# untitled.net
KiCad netlist of a schematic drawn in EAGLE
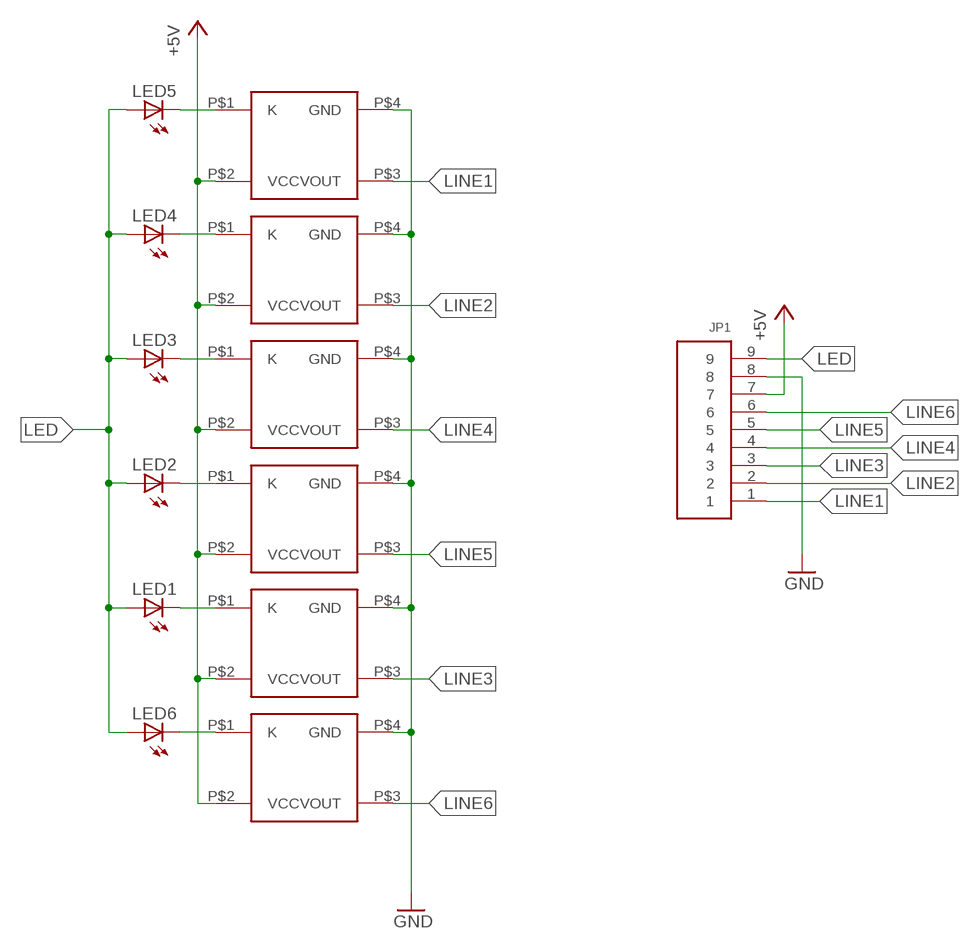
[diagram p0: schematic, sheet 1]

(export (version "E")
  (design (tool "Eeschema 10.0.6"))
  (components
    (comp (ref "JP1")
      (value "9PIN")
      (footprint "eagle-import:B9B-PH-K-S")
      (libsource (lib "eagle-import") (part "9PIN"))
    )
    (comp (ref "LED1")
      (value "LED5MM")
      (footprint "eagle-import:LED5MM")
      (libsource (lib "eagle-import") (part "LED5MM"))
    )
    (comp (ref "LED2")
      (value "LED5MM")
      (footprint "eagle-import:LED5MM")
      (libsource (lib "eagle-import") (part "LED5MM"))
    )
    (comp (ref "LED3")
      (value "LED5MM")
      (footprint "eagle-import:LED5MM")
      (libsource (lib "eagle-import") (part "LED5MM"))
    )
    (comp (ref "LED4")
      (value "LED5MM")
      (footprint "eagle-import:LED5MM")
      (libsource (lib "eagle-import") (part "LED5MM"))
    )
    (comp (ref "LED5")
      (value "LED5MM")
      (footprint "eagle-import:LED5MM")
      (libsource (lib "eagle-import") (part "LED5MM"))
    )
    (comp (ref "LED6")
      (value "LED5MM")
      (footprint "eagle-import:LED5MM")
      (libsource (lib "eagle-import") (part "LED5MM"))
    )
    (comp (ref "U$1")
      (value "S4282-51")
      (footprint "eagle-import:S4282-51")
      (libsource (lib "eagle-import") (part "S4282-51"))
    )
    (comp (ref "U$2")
      (value "S4282-51")
      (footprint "eagle-import:S4282-51")
      (libsource (lib "eagle-import") (part "S4282-51"))
    )
    (comp (ref "U$3")
      (value "S4282-51")
      (footprint "eagle-import:S4282-51")
      (libsource (lib "eagle-import") (part "S4282-51"))
    )
    (comp (ref "U$4")
      (value "S4282-51")
      (footprint "eagle-import:S4282-51")
      (libsource (lib "eagle-import") (part "S4282-51"))
    )
    (comp (ref "U$5")
      (value "S4282-51")
      (footprint "eagle-import:S4282-51")
      (libsource (lib "eagle-import") (part "S4282-51"))
    )
    (comp (ref "U$6")
      (value "S4282-51")
      (footprint "eagle-import:S4282-51")
      (libsource (lib "eagle-import") (part "S4282-51"))
    )
  )
  (nets
    (net (code "1") (name "+5V") (class "Default")
      (node (ref "JP1") (pin "7") (pinfunction "7_7") (pintype "bidirectional"))
      (node (ref "U$1") (pin "P$2") (pinfunction "VCC_P$2") (pintype "bidirectional"))
      (node (ref "U$2") (pin "P$2") (pinfunction "VCC_P$2") (pintype "bidirectional"))
      (node (ref "U$3") (pin "P$2") (pinfunction "VCC_P$2") (pintype "bidirectional"))
      (node (ref "U$4") (pin "P$2") (pinfunction "VCC_P$2") (pintype "bidirectional"))
      (node (ref "U$5") (pin "P$2") (pinfunction "VCC_P$2") (pintype "bidirectional"))
      (node (ref "U$6") (pin "P$2") (pinfunction "VCC_P$2") (pintype "bidirectional"))
    )
    (net (code "2") (name "GND") (class "Default")
      (node (ref "JP1") (pin "8") (pinfunction "8_8") (pintype "bidirectional"))
      (node (ref "U$1") (pin "P$4") (pinfunction "GND_P$4") (pintype "bidirectional"))
      (node (ref "U$2") (pin "P$4") (pinfunction "GND_P$4") (pintype "bidirectional"))
      (node (ref "U$3") (pin "P$4") (pinfunction "GND_P$4") (pintype "bidirectional"))
      (node (ref "U$4") (pin "P$4") (pinfunction "GND_P$4") (pintype "bidirectional"))
      (node (ref "U$5") (pin "P$4") (pinfunction "GND_P$4") (pintype "bidirectional"))
      (node (ref "U$6") (pin "P$4") (pinfunction "GND_P$4") (pintype "bidirectional"))
    )
    (net (code "3") (name "LED") (class "Default")
      (node (ref "JP1") (pin "9") (pinfunction "9_9") (pintype "bidirectional"))
      (node (ref "LED1") (pin "A") (pinfunction "A_A") (pintype "passive"))
      (node (ref "LED2") (pin "A") (pinfunction "A_A") (pintype "passive"))
      (node (ref "LED3") (pin "A") (pinfunction "A_A") (pintype "passive"))
      (node (ref "LED4") (pin "A") (pinfunction "A_A") (pintype "passive"))
      (node (ref "LED5") (pin "A") (pinfunction "A_A") (pintype "passive"))
      (node (ref "LED6") (pin "A") (pinfunction "A_A") (pintype "passive"))
    )
    (net (code "4") (name "LINE1") (class "Default")
      (node (ref "JP1") (pin "1") (pinfunction "1_1") (pintype "bidirectional"))
      (node (ref "U$1") (pin "P$3") (pinfunction "VOUT_P$3") (pintype "bidirectional"))
    )
    (net (code "5") (name "LINE2") (class "Default")
      (node (ref "JP1") (pin "2") (pinfunction "2_2") (pintype "bidirectional"))
      (node (ref "U$2") (pin "P$3") (pinfunction "VOUT_P$3") (pintype "bidirectional"))
    )
    (net (code "6") (name "LINE3") (class "Default")
      (node (ref "JP1") (pin "3") (pinfunction "3_3") (pintype "bidirectional"))
      (node (ref "U$5") (pin "P$3") (pinfunction "VOUT_P$3") (pintype "bidirectional"))
    )
    (net (code "7") (name "LINE4") (class "Default")
      (node (ref "JP1") (pin "4") (pinfunction "4_4") (pintype "bidirectional"))
      (node (ref "U$3") (pin "P$3") (pinfunction "VOUT_P$3") (pintype "bidirectional"))
    )
    (net (code "8") (name "LINE5") (class "Default")
      (node (ref "JP1") (pin "5") (pinfunction "5_5") (pintype "bidirectional"))
      (node (ref "U$4") (pin "P$3") (pinfunction "VOUT_P$3") (pintype "bidirectional"))
    )
    (net (code "9") (name "LINE6") (class "Default")
      (node (ref "JP1") (pin "6") (pinfunction "6_6") (pintype "bidirectional"))
      (node (ref "U$6") (pin "P$3") (pinfunction "VOUT_P$3") (pintype "bidirectional"))
    )
    (net (code "10") (name "Net-(LED1-C)") (class "Default")
      (node (ref "LED1") (pin "K") (pinfunction "C_K") (pintype "passive"))
      (node (ref "U$5") (pin "P$1") (pinfunction "K_P$1") (pintype "bidirectional"))
    )
    (net (code "11") (name "Net-(LED2-C)") (class "Default")
      (node (ref "LED2") (pin "K") (pinfunction "C_K") (pintype "passive"))
      (node (ref "U$4") (pin "P$1") (pinfunction "K_P$1") (pintype "bidirectional"))
    )
    (net (code "12") (name "Net-(LED3-C)") (class "Default")
      (node (ref "LED3") (pin "K") (pinfunction "C_K") (pintype "passive"))
      (node (ref "U$3") (pin "P$1") (pinfunction "K_P$1") (pintype "bidirectional"))
    )
    (net (code "13") (name "Net-(LED4-C)") (class "Default")
      (node (ref "LED4") (pin "K") (pinfunction "C_K") (pintype "passive"))
      (node (ref "U$2") (pin "P$1") (pinfunction "K_P$1") (pintype "bidirectional"))
    )
    (net (code "14") (name "Net-(LED5-C)") (class "Default")
      (node (ref "LED5") (pin "K") (pinfunction "C_K") (pintype "passive"))
      (node (ref "U$1") (pin "P$1") (pinfunction "K_P$1") (pintype "bidirectional"))
    )
    (net (code "15") (name "Net-(LED6-C)") (class "Default")
      (node (ref "LED6") (pin "K") (pinfunction "C_K") (pintype "passive"))
      (node (ref "U$6") (pin "P$1") (pinfunction "K_P$1") (pintype "bidirectional"))
    )
  )
)
